# board.net
KiCad netlist of a schematic drawn in EasyEDA Pro
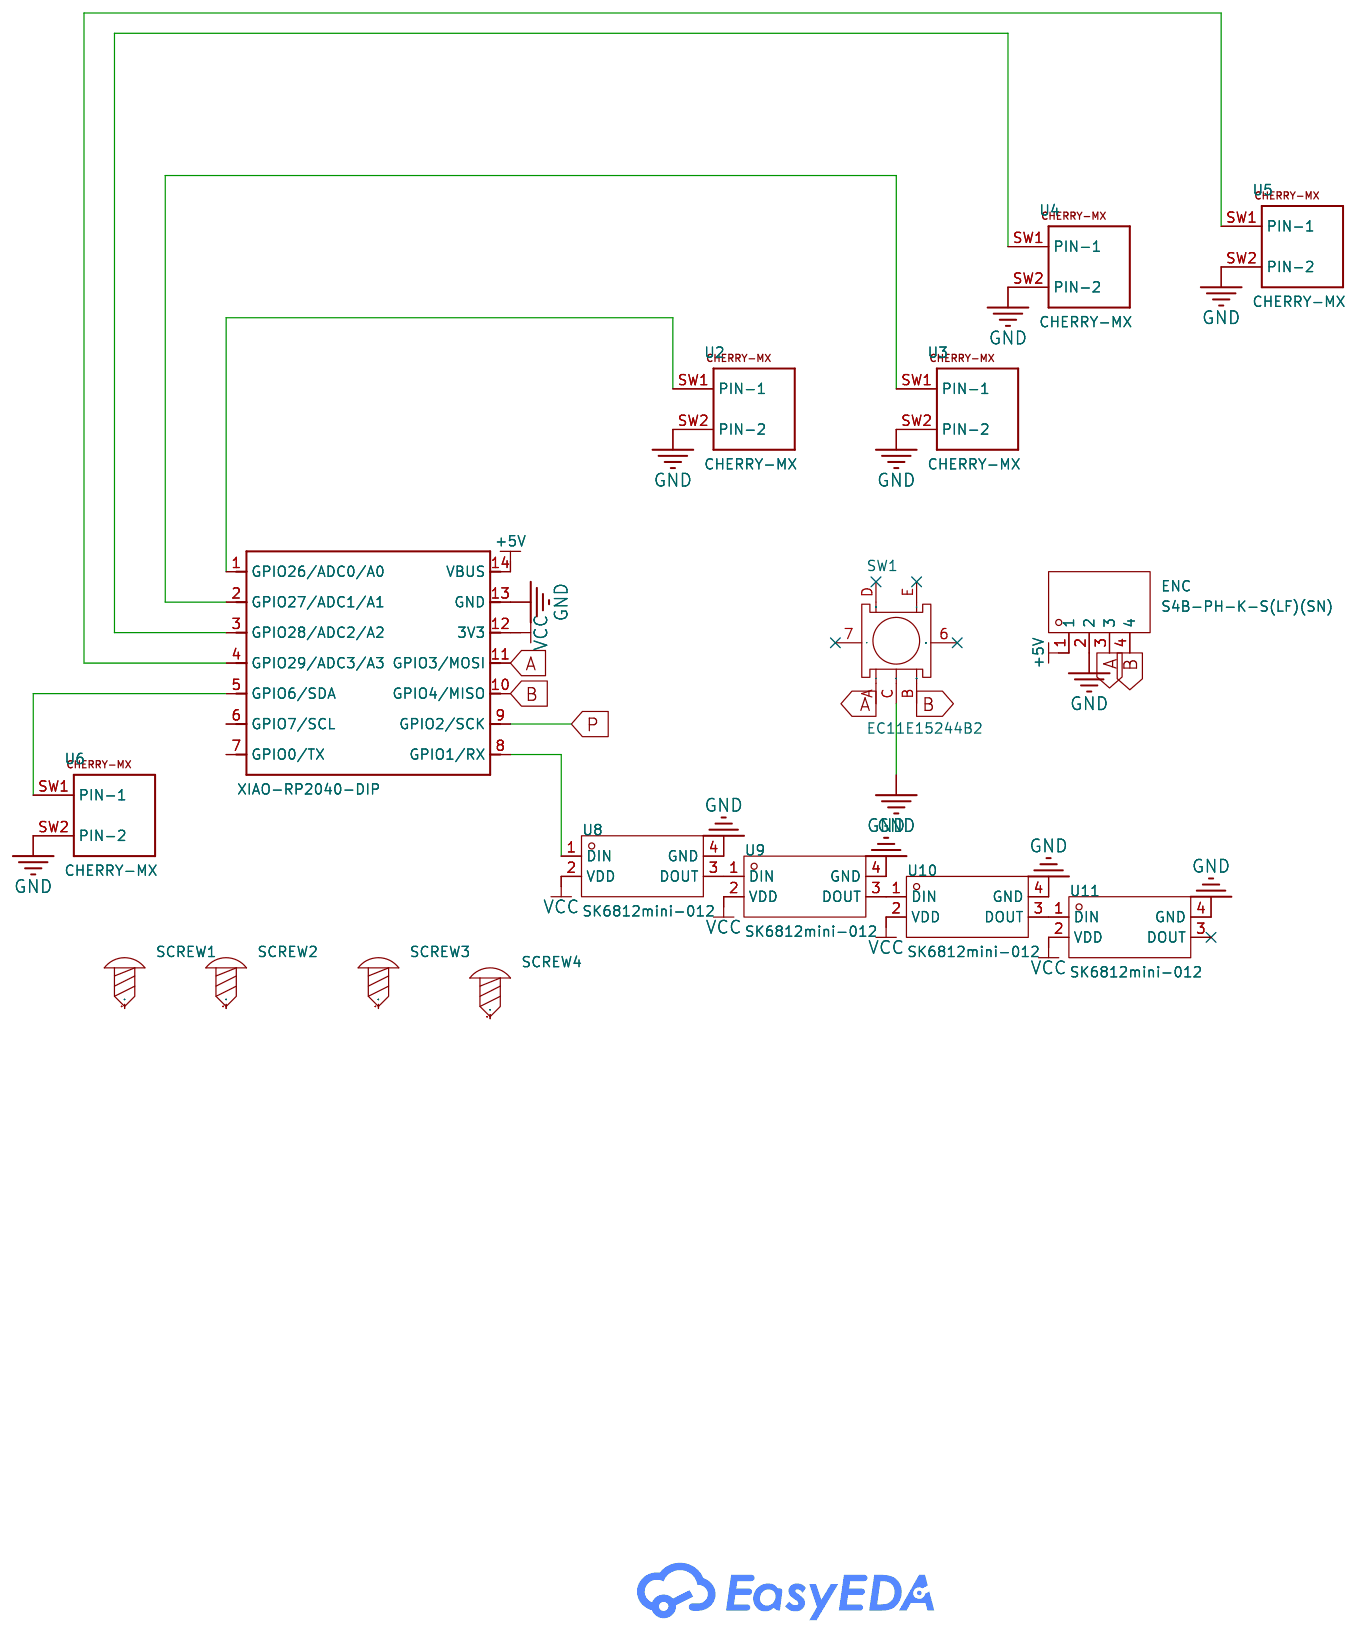
[diagram p0: schematic sheet]

(export (version "E")
  (design (tool "Eeschema 10.0.6"))
  (components
    (comp (ref "ENC")
      (value "S4B-PH-K-S(LF)(SN)")
      (footprint "easyedapro:CONN-TH_4P-P2.00_S4B-PH-K-S-LF-SN")
      (fields (field (name "Manufacturer") "JST"))
      (libsource (lib "easyedapro") (part "S4B-PH-K-S-(LF)(SN)"))
    )
    (comp (ref "SCREW1")
      (value "~")
      (footprint "easyedapro:Screw-Hole-M3")
      (libsource (lib "easyedapro") (part "Screw-Hole"))
    )
    (comp (ref "SCREW2")
      (value "~")
      (footprint "easyedapro:Screw-Hole-M3")
      (libsource (lib "easyedapro") (part "Screw-Hole"))
    )
    (comp (ref "SCREW3")
      (value "~")
      (footprint "easyedapro:Screw-Hole-M3")
      (libsource (lib "easyedapro") (part "Screw-Hole"))
    )
    (comp (ref "SCREW4")
      (value "~")
      (footprint "easyedapro:Screw-Hole-M3")
      (libsource (lib "easyedapro") (part "Screw-Hole"))
    )
    (comp (ref "SW1")
      (value "EC11E15244B2")
      (footprint "easyedapro:SW-TH_EC11XXXXXXXX")
      (fields (field (name "Manufacturer") "ALPSALPINE(阿尔卑斯阿尔派)"))
      (libsource (lib "easyedapro") (part "EC11E15244B2"))
    )
    (comp (ref "U1") (value "XIAO-RP2040-DIP") (libsource (lib "easyedapro") (part "XIAO-RP2040-DIP")))
    (comp (ref "U2")
      (value "CHERRY-MX")
      (footprint "easyedapro:CHERRY-MX")
      (libsource (lib "easyedapro") (part "CHERRY-MX"))
    )
    (comp (ref "U3")
      (value "CHERRY-MX")
      (footprint "easyedapro:CHERRY-MX")
      (libsource (lib "easyedapro") (part "CHERRY-MX"))
    )
    (comp (ref "U4")
      (value "CHERRY-MX")
      (footprint "easyedapro:CHERRY-MX")
      (libsource (lib "easyedapro") (part "CHERRY-MX"))
    )
    (comp (ref "U5")
      (value "CHERRY-MX")
      (footprint "easyedapro:CHERRY-MX")
      (libsource (lib "easyedapro") (part "CHERRY-MX"))
    )
    (comp (ref "U6")
      (value "CHERRY-MX")
      (footprint "easyedapro:CHERRY-MX")
      (libsource (lib "easyedapro") (part "CHERRY-MX"))
    )
    (comp (ref "U8")
      (value "SK6812mini-012")
      (footprint "easyedapro:LED-SMD_4P-L3.7-W3.5-P1.75-BR-SK6812MINI")
      (fields (field (name "Manufacturer") "欧思科光电"))
      (libsource (lib "easyedapro") (part "SK6812MINI"))
    )
    (comp (ref "U9")
      (value "SK6812mini-012")
      (footprint "easyedapro:LED-SMD_4P-L3.7-W3.5-P1.75-BR-SK6812MINI")
      (fields (field (name "Manufacturer") "欧思科光电"))
      (libsource (lib "easyedapro") (part "SK6812MINI"))
    )
    (comp (ref "U10")
      (value "SK6812mini-012")
      (footprint "easyedapro:LED-SMD_4P-L3.7-W3.5-P1.75-BR-SK6812MINI")
      (fields (field (name "Manufacturer") "欧思科光电"))
      (libsource (lib "easyedapro") (part "SK6812MINI"))
    )
    (comp (ref "U11")
      (value "SK6812mini-012")
      (footprint "easyedapro:LED-SMD_4P-L3.7-W3.5-P1.75-BR-SK6812MINI")
      (fields (field (name "Manufacturer") "欧思科光电"))
      (libsource (lib "easyedapro") (part "SK6812MINI"))
    )
  )
  (nets
    (net (code "1") (name "+5V") (class "Default")
      (node (ref "ENC") (pin "1") (pinfunction "1_1") (pintype "unspecified"))
      (node (ref "U1") (pin "14") (pinfunction "VBUS_14") (pintype "unspecified"))
    )
    (net (code "2") (name "A") (class "Default")
      (node (ref "ENC") (pin "3") (pinfunction "3_3") (pintype "unspecified"))
      (node (ref "SW1") (pin "A") (pinfunction "A_A") (pintype "unspecified"))
      (node (ref "U1") (pin "11") (pinfunction "GPIO3/MOSI_11") (pintype "unspecified"))
    )
    (net (code "3") (name "B") (class "Default")
      (node (ref "ENC") (pin "4") (pinfunction "4_4") (pintype "unspecified"))
      (node (ref "SW1") (pin "B") (pinfunction "B_B") (pintype "unspecified"))
      (node (ref "U1") (pin "10") (pinfunction "GPIO4/MISO_10") (pintype "unspecified"))
    )
    (net (code "4") (name "GND") (class "Default")
      (node (ref "ENC") (pin "2") (pinfunction "2_2") (pintype "unspecified"))
      (node (ref "SW1") (pin "C") (pinfunction "C_C") (pintype "unspecified"))
      (node (ref "U1") (pin "13") (pinfunction "GND_13") (pintype "unspecified"))
      (node (ref "U10") (pin "4") (pinfunction "GND_4") (pintype "unspecified"))
      (node (ref "U11") (pin "4") (pinfunction "GND_4") (pintype "unspecified"))
      (node (ref "U2") (pin "SW2") (pinfunction "PIN-2_SW2") (pintype "bidirectional"))
      (node (ref "U3") (pin "SW2") (pinfunction "PIN-2_SW2") (pintype "bidirectional"))
      (node (ref "U4") (pin "SW2") (pinfunction "PIN-2_SW2") (pintype "bidirectional"))
      (node (ref "U5") (pin "SW2") (pinfunction "PIN-2_SW2") (pintype "bidirectional"))
      (node (ref "U6") (pin "SW2") (pinfunction "PIN-2_SW2") (pintype "bidirectional"))
      (node (ref "U8") (pin "4") (pinfunction "GND_4") (pintype "unspecified"))
      (node (ref "U9") (pin "4") (pinfunction "GND_4") (pintype "unspecified"))
    )
    (net (code "5") (name "Net-(U1-GPIO1{slash}RX)") (class "Default")
      (node (ref "U1") (pin "8") (pinfunction "GPIO1/RX_8") (pintype "unspecified"))
      (node (ref "U8") (pin "1") (pinfunction "DIN_1") (pintype "unspecified"))
    )
    (net (code "6") (name "Net-(U1-GPIO6{slash}SDA)") (class "Default")
      (node (ref "U1") (pin "5") (pinfunction "GPIO6/SDA_5") (pintype "unspecified"))
      (node (ref "U6") (pin "SW1") (pinfunction "PIN-1_SW1") (pintype "bidirectional"))
    )
    (net (code "7") (name "Net-(U1-GPIO26{slash}ADC0{slash}A0)") (class "Default")
      (node (ref "U1") (pin "1") (pinfunction "GPIO26/ADC0/A0_1") (pintype "unspecified"))
      (node (ref "U2") (pin "SW1") (pinfunction "PIN-1_SW1") (pintype "bidirectional"))
    )
    (net (code "8") (name "Net-(U1-GPIO27{slash}ADC1{slash}A1)") (class "Default")
      (node (ref "U1") (pin "2") (pinfunction "GPIO27/ADC1/A1_2") (pintype "unspecified"))
      (node (ref "U3") (pin "SW1") (pinfunction "PIN-1_SW1") (pintype "bidirectional"))
    )
    (net (code "9") (name "Net-(U1-GPIO28{slash}ADC2{slash}A2)") (class "Default")
      (node (ref "U1") (pin "3") (pinfunction "GPIO28/ADC2/A2_3") (pintype "unspecified"))
      (node (ref "U4") (pin "SW1") (pinfunction "PIN-1_SW1") (pintype "bidirectional"))
    )
    (net (code "10") (name "Net-(U1-GPIO29{slash}ADC3{slash}A3)") (class "Default")
      (node (ref "U1") (pin "4") (pinfunction "GPIO29/ADC3/A3_4") (pintype "unspecified"))
      (node (ref "U5") (pin "SW1") (pinfunction "PIN-1_SW1") (pintype "bidirectional"))
    )
    (net (code "11") (name "Net-(U8-DOUT)") (class "Default")
      (node (ref "U8") (pin "3") (pinfunction "DOUT_3") (pintype "unspecified"))
      (node (ref "U9") (pin "1") (pinfunction "DIN_1") (pintype "unspecified"))
    )
    (net (code "12") (name "Net-(U10-DIN)") (class "Default")
      (node (ref "U10") (pin "1") (pinfunction "DIN_1") (pintype "unspecified"))
      (node (ref "U9") (pin "3") (pinfunction "DOUT_3") (pintype "unspecified"))
    )
    (net (code "13") (name "Net-(U10-DOUT)") (class "Default")
      (node (ref "U10") (pin "3") (pinfunction "DOUT_3") (pintype "unspecified"))
      (node (ref "U11") (pin "1") (pinfunction "DIN_1") (pintype "unspecified"))
    )
    (net (code "14") (name "P") (class "Default")
      (node (ref "U1") (pin "9") (pinfunction "GPIO2/SCK_9") (pintype "unspecified"))
    )
    (net (code "15") (name "VCC") (class "Default")
      (node (ref "U1") (pin "12") (pinfunction "3V3_12") (pintype "unspecified"))
      (node (ref "U10") (pin "2") (pinfunction "VDD_2") (pintype "unspecified"))
      (node (ref "U11") (pin "2") (pinfunction "VDD_2") (pintype "unspecified"))
      (node (ref "U8") (pin "2") (pinfunction "VDD_2") (pintype "unspecified"))
      (node (ref "U9") (pin "2") (pinfunction "VDD_2") (pintype "unspecified"))
    )
    (net (code "16") (name "unconnected-(SCREW1-Pad1)") (class "Default")
      (node (ref "SCREW1") (pin "1") (pinfunction "1_1") (pintype "input"))
    )
    (net (code "17") (name "unconnected-(SCREW2-Pad1)") (class "Default")
      (node (ref "SCREW2") (pin "1") (pinfunction "1_1") (pintype "input"))
    )
    (net (code "18") (name "unconnected-(SCREW3-Pad1)") (class "Default")
      (node (ref "SCREW3") (pin "1") (pinfunction "1_1") (pintype "input"))
    )
    (net (code "19") (name "unconnected-(SCREW4-Pad1)") (class "Default")
      (node (ref "SCREW4") (pin "1") (pinfunction "1_1") (pintype "input"))
    )
    (net (code "20") (name "unconnected-(SW1-Pad6)") (class "Default")
      (node (ref "SW1") (pin "6") (pinfunction "6_6") (pintype "unspecified+no_connect"))
    )
    (net (code "21") (name "unconnected-(SW1-Pad7)") (class "Default")
      (node (ref "SW1") (pin "7") (pinfunction "7_7") (pintype "unspecified+no_connect"))
    )
    (net (code "22") (name "unconnected-(SW1-PadD)") (class "Default")
      (node (ref "SW1") (pin "D") (pinfunction "D_D") (pintype "unspecified+no_connect"))
    )
    (net (code "23") (name "unconnected-(SW1-PadE)") (class "Default")
      (node (ref "SW1") (pin "E") (pinfunction "E_E") (pintype "unspecified+no_connect"))
    )
    (net (code "24") (name "unconnected-(U1-GPIO0{slash}TX-Pad7)") (class "Default")
      (node (ref "U1") (pin "7") (pinfunction "GPIO0/TX_7") (pintype "unspecified"))
    )
    (net (code "25") (name "unconnected-(U1-GPIO7{slash}SCL-Pad6)") (class "Default")
      (node (ref "U1") (pin "6") (pinfunction "GPIO7/SCL_6") (pintype "unspecified"))
    )
    (net (code "26") (name "unconnected-(U11-DOUT-Pad3)") (class "Default")
      (node (ref "U11") (pin "3") (pinfunction "DOUT_3") (pintype "unspecified+no_connect"))
    )
  )
)
